# 4_Expansion.net
KiCad netlist of a schematic drawn in Altium Designer
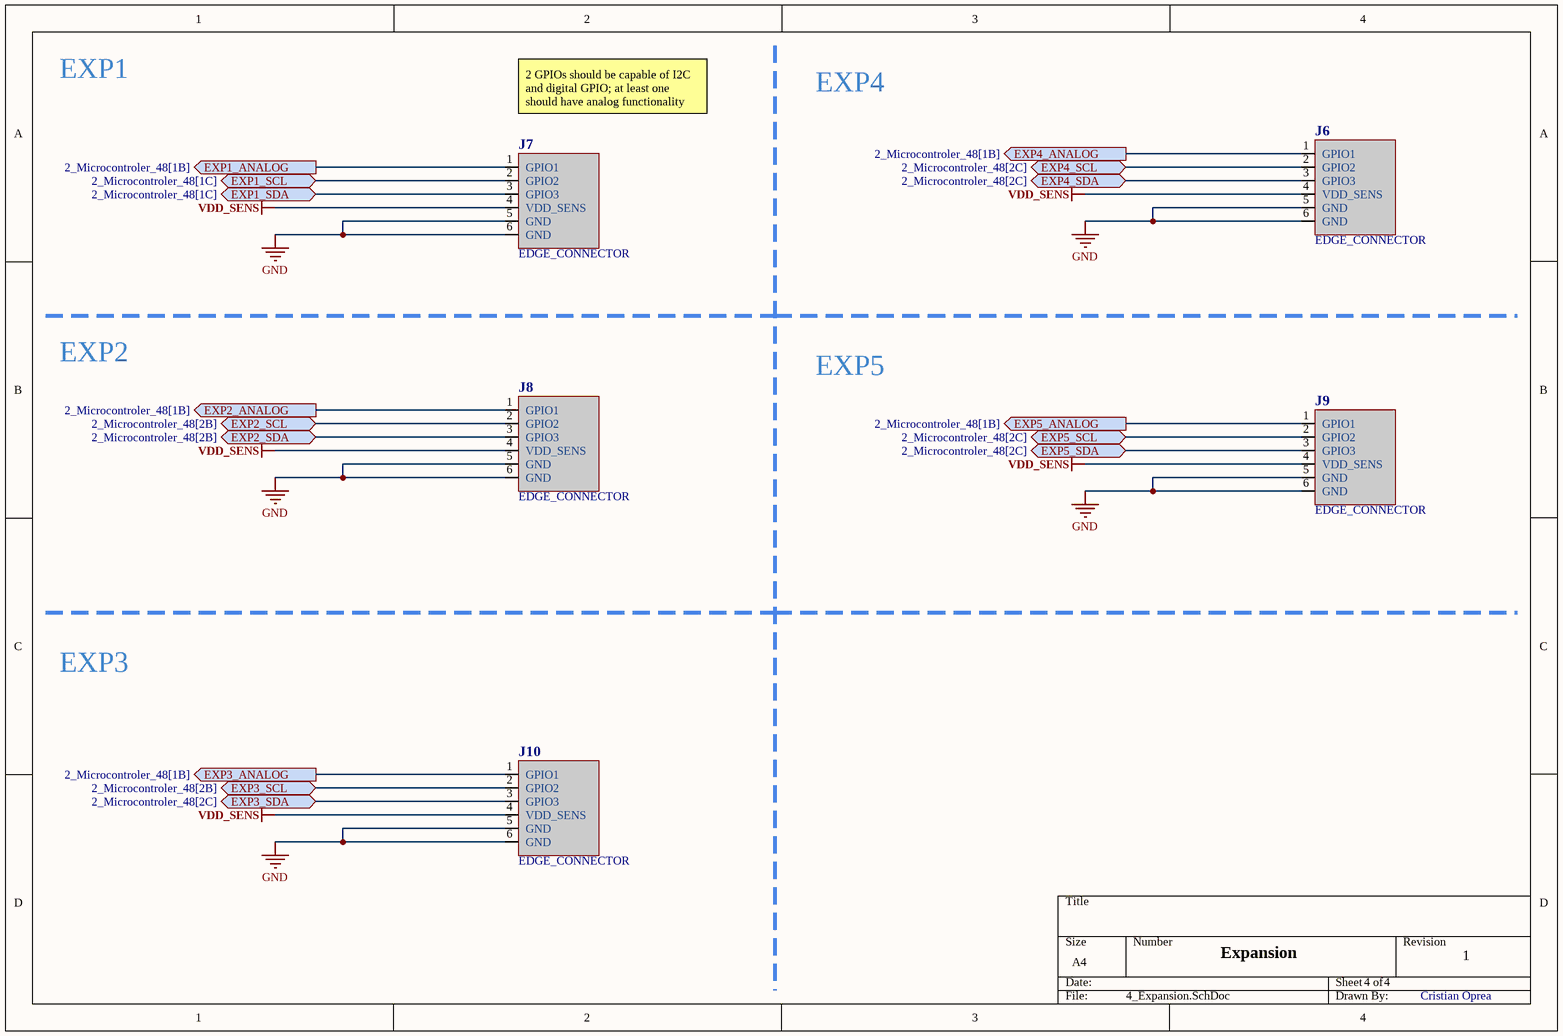
[diagram p0: 4_Expansion.SchDoc]

(export (version "E")
  (design (tool "Eeschema 10.0.6"))
  (components
    (comp (ref "J6")
      (value "EDGE_CONNECTOR")
      (footprint "2.54mm_edge_connector")
      (description "Connector for sensor modules")
      (libsource (lib "Schlib_H2") (part "edge_connector"))
    )
    (comp (ref "J7")
      (value "EDGE_CONNECTOR")
      (footprint "2.54mm_edge_connector")
      (description "Connector for sensor modules")
      (libsource (lib "Schlib_H2") (part "edge_connector"))
    )
    (comp (ref "J8")
      (value "EDGE_CONNECTOR")
      (footprint "2.54mm_edge_connector")
      (description "Connector for sensor modules")
      (libsource (lib "Schlib_H2") (part "edge_connector"))
    )
    (comp (ref "J9")
      (value "EDGE_CONNECTOR")
      (footprint "2.54mm_edge_connector")
      (description "Connector for sensor modules")
      (libsource (lib "Schlib_H2") (part "edge_connector"))
    )
    (comp (ref "J10")
      (value "EDGE_CONNECTOR")
      (footprint "2.54mm_edge_connector")
      (description "Connector for sensor modules")
      (libsource (lib "Schlib_H2") (part "edge_connector"))
    )
  )
  (nets
    (net (code "1") (name "/EXP1_ANALOG") (class "Default")
      (node (ref "J7") (pin "1") (pinfunction "GPIO1_1") (pintype "passive"))
    )
    (net (code "2") (name "/EXP1_SCL") (class "Default")
      (node (ref "J7") (pin "2") (pinfunction "GPIO2_2") (pintype "passive"))
    )
    (net (code "3") (name "/EXP1_SDA") (class "Default")
      (node (ref "J7") (pin "3") (pinfunction "GPIO3_3") (pintype "passive"))
    )
    (net (code "4") (name "/EXP2_ANALOG") (class "Default")
      (node (ref "J8") (pin "1") (pinfunction "GPIO1_1") (pintype "passive"))
    )
    (net (code "5") (name "/EXP2_SCL") (class "Default")
      (node (ref "J8") (pin "2") (pinfunction "GPIO2_2") (pintype "passive"))
    )
    (net (code "6") (name "/EXP2_SDA") (class "Default")
      (node (ref "J8") (pin "3") (pinfunction "GPIO3_3") (pintype "passive"))
    )
    (net (code "7") (name "/EXP3_ANALOG") (class "Default")
      (node (ref "J10") (pin "1") (pinfunction "GPIO1_1") (pintype "passive"))
    )
    (net (code "8") (name "/EXP3_SCL") (class "Default")
      (node (ref "J10") (pin "2") (pinfunction "GPIO2_2") (pintype "passive"))
    )
    (net (code "9") (name "/EXP3_SDA") (class "Default")
      (node (ref "J10") (pin "3") (pinfunction "GPIO3_3") (pintype "passive"))
    )
    (net (code "10") (name "/EXP4_ANALOG") (class "Default")
      (node (ref "J6") (pin "1") (pinfunction "GPIO1_1") (pintype "passive"))
    )
    (net (code "11") (name "/EXP4_SCL") (class "Default")
      (node (ref "J6") (pin "2") (pinfunction "GPIO2_2") (pintype "passive"))
    )
    (net (code "12") (name "/EXP4_SDA") (class "Default")
      (node (ref "J6") (pin "3") (pinfunction "GPIO3_3") (pintype "passive"))
    )
    (net (code "13") (name "/EXP5_ANALOG") (class "Default")
      (node (ref "J9") (pin "1") (pinfunction "GPIO1_1") (pintype "passive"))
    )
    (net (code "14") (name "/EXP5_SCL") (class "Default")
      (node (ref "J9") (pin "2") (pinfunction "GPIO2_2") (pintype "passive"))
    )
    (net (code "15") (name "/EXP5_SDA") (class "Default")
      (node (ref "J9") (pin "3") (pinfunction "GPIO3_3") (pintype "passive"))
    )
    (net (code "16") (name "GND") (class "Default")
      (node (ref "J10") (pin "5") (pinfunction "GND_5") (pintype "passive"))
      (node (ref "J10") (pin "6") (pinfunction "GND_6") (pintype "passive"))
      (node (ref "J6") (pin "5") (pinfunction "GND_5") (pintype "passive"))
      (node (ref "J6") (pin "6") (pinfunction "GND_6") (pintype "passive"))
      (node (ref "J7") (pin "5") (pinfunction "GND_5") (pintype "passive"))
      (node (ref "J7") (pin "6") (pinfunction "GND_6") (pintype "passive"))
      (node (ref "J8") (pin "5") (pinfunction "GND_5") (pintype "passive"))
      (node (ref "J8") (pin "6") (pinfunction "GND_6") (pintype "passive"))
      (node (ref "J9") (pin "5") (pinfunction "GND_5") (pintype "passive"))
      (node (ref "J9") (pin "6") (pinfunction "GND_6") (pintype "passive"))
    )
    (net (code "17") (name "VDD_SENS") (class "Default")
      (node (ref "J10") (pin "4") (pinfunction "VDD_SENS_4") (pintype "passive"))
      (node (ref "J6") (pin "4") (pinfunction "VDD_SENS_4") (pintype "passive"))
      (node (ref "J7") (pin "4") (pinfunction "VDD_SENS_4") (pintype "passive"))
      (node (ref "J8") (pin "4") (pinfunction "VDD_SENS_4") (pintype "passive"))
      (node (ref "J9") (pin "4") (pinfunction "VDD_SENS_4") (pintype "passive"))
    )
  )
)
